# Adafruit_LSM9DS1_Rev_A.net
KiCad netlist of a schematic drawn in EAGLE
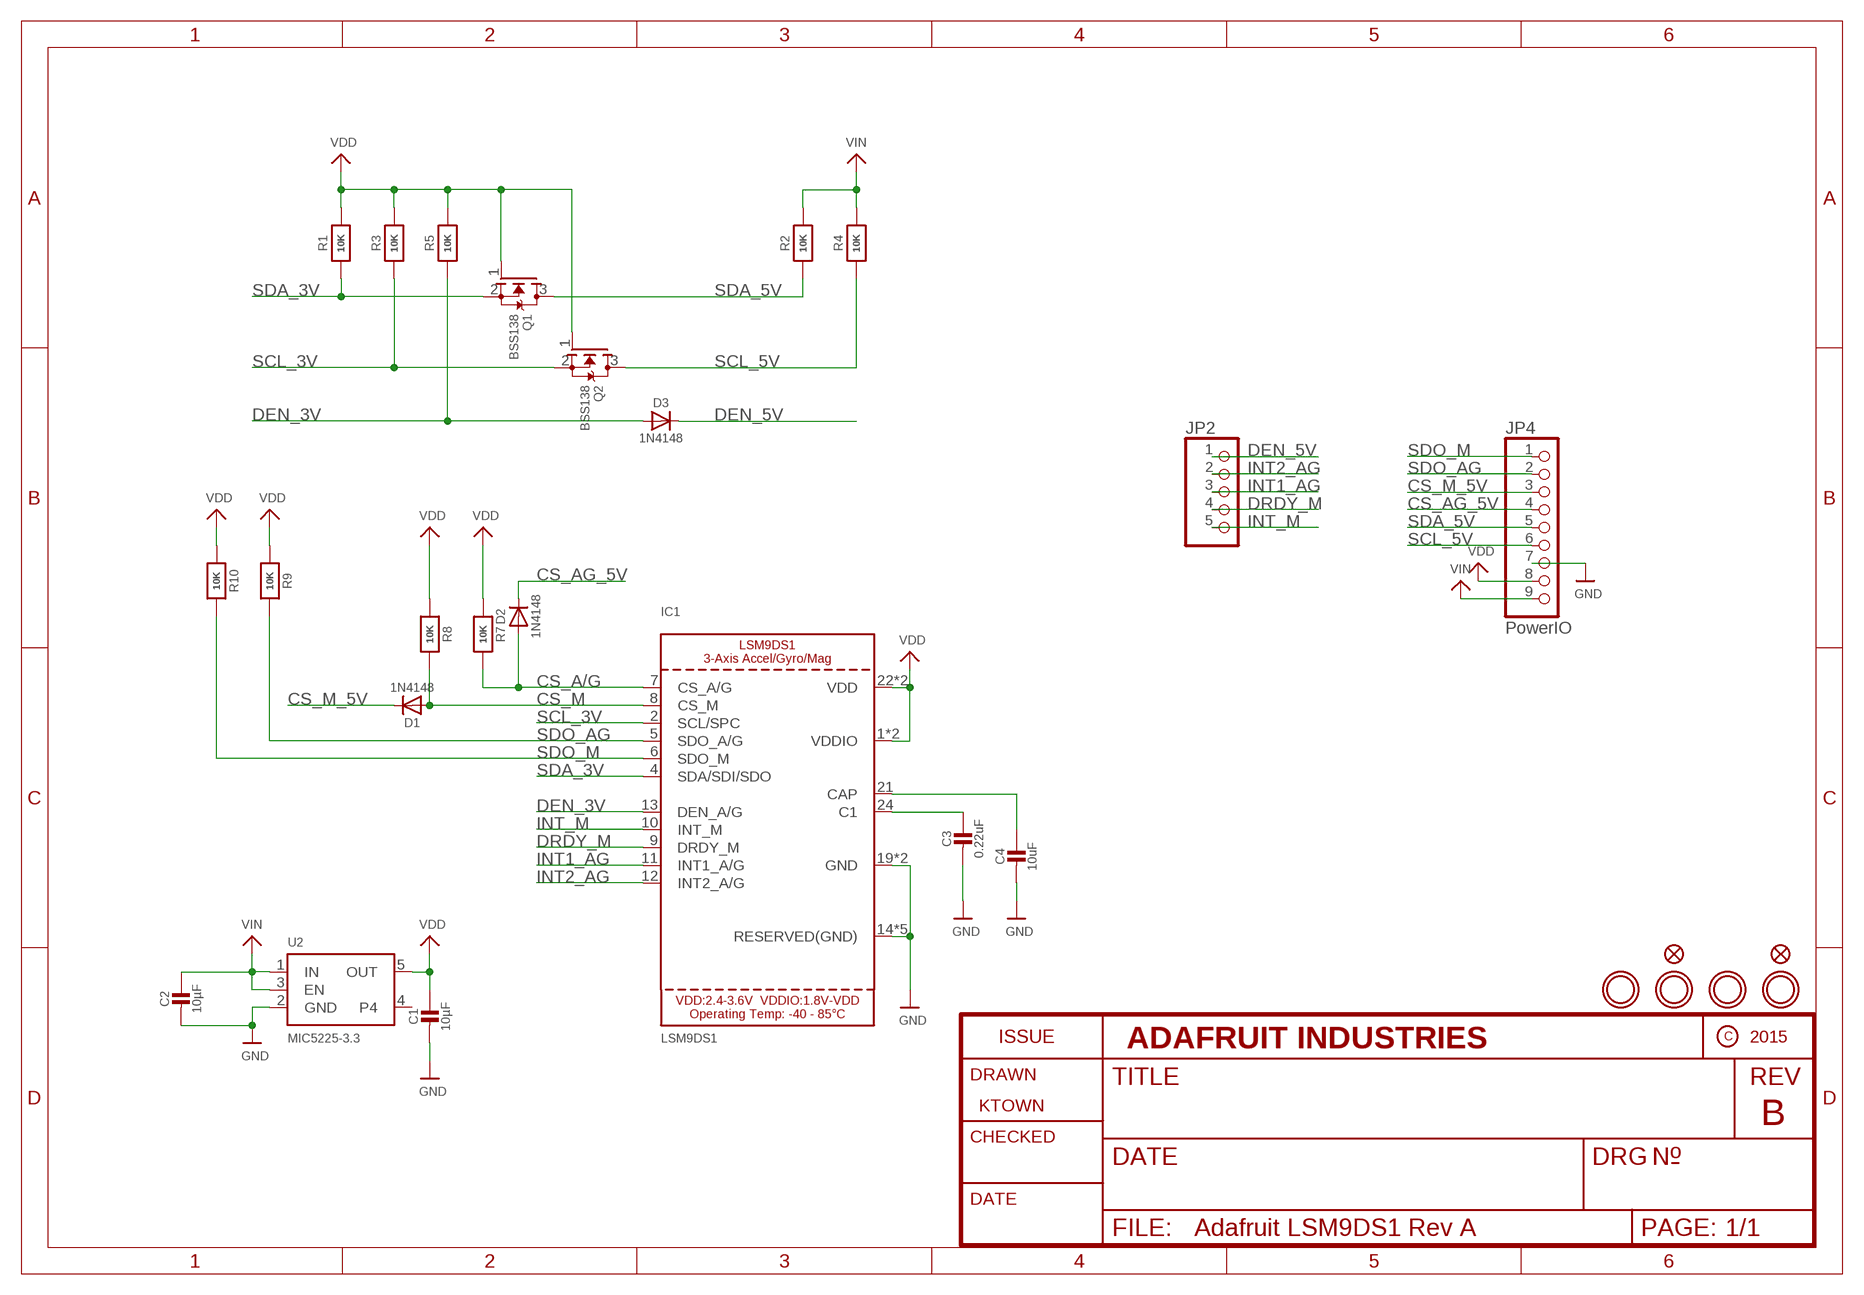
[diagram p0: schematic, sheet 1]

(export (version "E")
  (design (tool "Eeschema 10.0.6"))
  (components
    (comp (ref "C1")
      (value "10µF")
      (footprint "eagle-import:0805-NO")
      (libsource (lib "eagle-import") (part "CAP_CERAMIC0805-NOOUTLINE"))
    )
    (comp (ref "C2")
      (value "10µF")
      (footprint "eagle-import:0805-NO")
      (libsource (lib "eagle-import") (part "CAP_CERAMIC0805-NOOUTLINE"))
    )
    (comp (ref "C3")
      (value "0.22uF")
      (footprint "eagle-import:0805_10MGAP")
      (libsource (lib "eagle-import") (part "CAP_CERAMIC0805_10MGAP"))
    )
    (comp (ref "C4")
      (value "10uF")
      (footprint "eagle-import:0805-NO")
      (libsource (lib "eagle-import") (part "CAP_CERAMIC0805-NOOUTLINE"))
    )
    (comp (ref "D1")
      (value "1N4148")
      (footprint "eagle-import:SOD-323")
      (libsource (lib "eagle-import") (part "DIODESOD-323"))
    )
    (comp (ref "D2")
      (value "1N4148")
      (footprint "eagle-import:SOD-323")
      (libsource (lib "eagle-import") (part "DIODESOD-323"))
    )
    (comp (ref "D3")
      (value "1N4148")
      (footprint "eagle-import:SOD-323")
      (libsource (lib "eagle-import") (part "DIODESOD-323"))
    )
    (comp (ref "FID1")
      (value "FIDUCIAL\"\"")
      (footprint "eagle-import:FIDUCIAL_1MM")
      (libsource (lib "eagle-import") (part "FIDUCIAL{dblquote}{dblquote}"))
    )
    (comp (ref "FID3")
      (value "FIDUCIAL\"\"")
      (footprint "eagle-import:FIDUCIAL_1MM")
      (fields (field (name "BOM") "EXCLUDE"))
      (libsource (lib "eagle-import") (part "FIDUCIAL{dblquote}{dblquote}"))
    )
    (comp (ref "IC1")
      (value "LSM9DS1")
      (footprint "eagle-import:LGA24_3.5X3.1MM")
      (libsource (lib "eagle-import") (part "LSM9DS1"))
    )
    (comp (ref "JP2")
      (value "HEADER-1X570MIL")
      (footprint "eagle-import:1X05_ROUND_70")
      (libsource (lib "eagle-import") (part "HEADER-1X570MIL"))
    )
    (comp (ref "JP4")
      (value "PowerIO")
      (footprint "eagle-import:1X09_ROUND_70")
      (libsource (lib "eagle-import") (part "HEADER-1X970MIL"))
    )
    (comp (ref "Q1")
      (value "BSS138")
      (footprint "eagle-import:SOT23-WIDE")
      (libsource (lib "eagle-import") (part "MOSFET-NWIDE"))
    )
    (comp (ref "Q2")
      (value "BSS138")
      (footprint "eagle-import:SOT23-WIDE")
      (libsource (lib "eagle-import") (part "MOSFET-NWIDE"))
    )
    (comp (ref "R1")
      (value "10K")
      (footprint "eagle-import:0805_10MGAP")
      (libsource (lib "eagle-import") (part "RESISTOR0805_10MGAP"))
    )
    (comp (ref "R2")
      (value "10K")
      (footprint "eagle-import:0805-NO")
      (libsource (lib "eagle-import") (part "RESISTOR0805_NOOUTLINE"))
    )
    (comp (ref "R3")
      (value "10K")
      (footprint "eagle-import:0805-NO")
      (libsource (lib "eagle-import") (part "RESISTOR0805_NOOUTLINE"))
    )
    (comp (ref "R4")
      (value "10K")
      (footprint "eagle-import:0805-NO")
      (libsource (lib "eagle-import") (part "RESISTOR0805_NOOUTLINE"))
    )
    (comp (ref "R5")
      (value "10K")
      (footprint "eagle-import:0805-NO")
      (libsource (lib "eagle-import") (part "RESISTOR0805_NOOUTLINE"))
    )
    (comp (ref "R7")
      (value "10K")
      (footprint "eagle-import:0805-NO")
      (libsource (lib "eagle-import") (part "RESISTOR0805_NOOUTLINE"))
    )
    (comp (ref "R8")
      (value "10K")
      (footprint "eagle-import:0805-NO")
      (libsource (lib "eagle-import") (part "RESISTOR0805_NOOUTLINE"))
    )
    (comp (ref "R9")
      (value "10K")
      (footprint "eagle-import:0805_10MGAP")
      (libsource (lib "eagle-import") (part "RESISTOR0805_10MGAP"))
    )
    (comp (ref "R10")
      (value "10K")
      (footprint "eagle-import:0805-NO")
      (libsource (lib "eagle-import") (part "RESISTOR0805_NOOUTLINE"))
    )
    (comp (ref "U$4")
      (value "MOUNTINGHOLE2.5")
      (footprint "eagle-import:MOUNTINGHOLE_2.5_PLATED")
      (libsource (lib "eagle-import") (part "MOUNTINGHOLE2.5"))
    )
    (comp (ref "U$5")
      (value "MOUNTINGHOLE2.5")
      (footprint "eagle-import:MOUNTINGHOLE_2.5_PLATED")
      (libsource (lib "eagle-import") (part "MOUNTINGHOLE2.5"))
    )
    (comp (ref "U$6")
      (value "MOUNTINGHOLE2.5")
      (footprint "eagle-import:MOUNTINGHOLE_2.5_PLATED")
      (libsource (lib "eagle-import") (part "MOUNTINGHOLE2.5"))
    )
    (comp (ref "U$7")
      (value "MOUNTINGHOLE2.5")
      (footprint "eagle-import:MOUNTINGHOLE_2.5_PLATED")
      (libsource (lib "eagle-import") (part "MOUNTINGHOLE2.5"))
    )
    (comp (ref "U2")
      (value "MIC5225-3.3")
      (footprint "eagle-import:SOT23-5")
      (libsource (lib "eagle-import") (part "VREG_SOT23-5"))
    )
  )
  (nets
    (net (code "1") (name "/CS_AG_5V") (class "Default")
      (node (ref "D2") (pin "C") (pinfunction "C_C") (pintype "passive"))
      (node (ref "JP4") (pin "4") (pinfunction "4_4") (pintype "passive"))
    )
    (net (code "2") (name "/CS_A{slash}G") (class "Default")
      (node (ref "D2") (pin "A") (pinfunction "A_A") (pintype "passive"))
      (node (ref "IC1") (pin "7") (pinfunction "CS_A/G_7") (pintype "bidirectional"))
      (node (ref "R7") (pin "2") (pinfunction "2_2") (pintype "passive"))
    )
    (net (code "3") (name "/CS_M") (class "Default")
      (node (ref "D1") (pin "A") (pinfunction "A_A") (pintype "passive"))
      (node (ref "IC1") (pin "8") (pinfunction "CS_M_8") (pintype "bidirectional"))
      (node (ref "R8") (pin "2") (pinfunction "2_2") (pintype "passive"))
    )
    (net (code "4") (name "/CS_M_5V") (class "Default")
      (node (ref "D1") (pin "C") (pinfunction "C_C") (pintype "passive"))
      (node (ref "JP4") (pin "3") (pinfunction "3_3") (pintype "passive"))
    )
    (net (code "5") (name "/DEN_3V") (class "Default")
      (node (ref "D3") (pin "A") (pinfunction "A_A") (pintype "passive"))
      (node (ref "IC1") (pin "13") (pinfunction "DEN_A/G_13") (pintype "bidirectional"))
      (node (ref "R5") (pin "1") (pinfunction "1_1") (pintype "passive"))
    )
    (net (code "6") (name "/DEN_5V") (class "Default")
      (node (ref "D3") (pin "C") (pinfunction "C_C") (pintype "passive"))
      (node (ref "JP2") (pin "1") (pinfunction "1_1") (pintype "passive"))
    )
    (net (code "7") (name "/DRDY_M") (class "Default")
      (node (ref "IC1") (pin "9") (pinfunction "DRDY_M_9") (pintype "bidirectional"))
      (node (ref "JP2") (pin "4") (pinfunction "4_4") (pintype "passive"))
    )
    (net (code "8") (name "/INT1_AG") (class "Default")
      (node (ref "IC1") (pin "11") (pinfunction "INT1_A/G_11") (pintype "bidirectional"))
      (node (ref "JP2") (pin "3") (pinfunction "3_3") (pintype "passive"))
    )
    (net (code "9") (name "/INT2_AG") (class "Default")
      (node (ref "IC1") (pin "12") (pinfunction "INT2_A/G_12") (pintype "bidirectional"))
      (node (ref "JP2") (pin "2") (pinfunction "2_2") (pintype "passive"))
    )
    (net (code "10") (name "/INT_M") (class "Default")
      (node (ref "IC1") (pin "10") (pinfunction "INT_M_10") (pintype "bidirectional"))
      (node (ref "JP2") (pin "5") (pinfunction "5_5") (pintype "passive"))
    )
    (net (code "11") (name "/SCL_3V") (class "Default")
      (node (ref "IC1") (pin "2") (pinfunction "SCL/SPC_2") (pintype "bidirectional"))
      (node (ref "Q2") (pin "2") (pinfunction "S_2") (pintype "bidirectional"))
      (node (ref "R3") (pin "1") (pinfunction "1_1") (pintype "passive"))
    )
    (net (code "12") (name "/SCL_5V") (class "Default")
      (node (ref "JP4") (pin "6") (pinfunction "6_6") (pintype "passive"))
      (node (ref "Q2") (pin "3") (pinfunction "D_3") (pintype "bidirectional"))
      (node (ref "R4") (pin "1") (pinfunction "1_1") (pintype "passive"))
    )
    (net (code "13") (name "/SDA_3V") (class "Default")
      (node (ref "IC1") (pin "4") (pinfunction "SDA/SDI/SDO_4") (pintype "bidirectional"))
      (node (ref "Q1") (pin "2") (pinfunction "S_2") (pintype "bidirectional"))
      (node (ref "R1") (pin "1") (pinfunction "1_1") (pintype "passive"))
    )
    (net (code "14") (name "/SDA_5V") (class "Default")
      (node (ref "JP4") (pin "5") (pinfunction "5_5") (pintype "passive"))
      (node (ref "Q1") (pin "3") (pinfunction "D_3") (pintype "bidirectional"))
      (node (ref "R2") (pin "1") (pinfunction "1_1") (pintype "passive"))
    )
    (net (code "15") (name "/SDO_AG") (class "Default")
      (node (ref "IC1") (pin "5") (pinfunction "SDO_A/G_5") (pintype "bidirectional"))
      (node (ref "JP4") (pin "2") (pinfunction "2_2") (pintype "passive"))
      (node (ref "R9") (pin "2") (pinfunction "2_2") (pintype "passive"))
    )
    (net (code "16") (name "/SDO_M") (class "Default")
      (node (ref "IC1") (pin "6") (pinfunction "SDO_M_6") (pintype "bidirectional"))
      (node (ref "JP4") (pin "1") (pinfunction "1_1") (pintype "passive"))
      (node (ref "R10") (pin "2") (pinfunction "2_2") (pintype "passive"))
    )
    (net (code "17") (name "GND") (class "Default")
      (node (ref "C1") (pin "2") (pinfunction "2_2") (pintype "passive"))
      (node (ref "C2") (pin "2") (pinfunction "2_2") (pintype "passive"))
      (node (ref "C3") (pin "2") (pinfunction "2_2") (pintype "passive"))
      (node (ref "C4") (pin "2") (pinfunction "2_2") (pintype "passive"))
      (node (ref "IC1") (pin "14") (pinfunction "RESERVED(GND)_14") (pintype "power_in"))
      (node (ref "IC1") (pin "15") (pinfunction "RESERVED(GND)_15") (pintype "power_in"))
      (node (ref "IC1") (pin "16") (pinfunction "RESERVED(GND)_16") (pintype "power_in"))
      (node (ref "IC1") (pin "17") (pinfunction "RESERVED(GND)_17") (pintype "power_in"))
      (node (ref "IC1") (pin "18") (pinfunction "RESERVED(GND)_18") (pintype "power_in"))
      (node (ref "IC1") (pin "19") (pinfunction "GND_19") (pintype "power_in"))
      (node (ref "IC1") (pin "20") (pinfunction "GND_20") (pintype "power_in"))
      (node (ref "JP4") (pin "7") (pinfunction "7_7") (pintype "passive"))
      (node (ref "U2") (pin "2") (pinfunction "GND_2") (pintype "power_in"))
    )
    (net (code "18") (name "Net-(IC1-C1)") (class "Default")
      (node (ref "C3") (pin "1") (pinfunction "1_1") (pintype "passive"))
      (node (ref "IC1") (pin "24") (pinfunction "C1_24") (pintype "bidirectional"))
    )
    (net (code "19") (name "Net-(IC1-CAP)") (class "Default")
      (node (ref "C4") (pin "1") (pinfunction "1_1") (pintype "passive"))
      (node (ref "IC1") (pin "21") (pinfunction "CAP_21") (pintype "bidirectional"))
    )
    (net (code "20") (name "VDD") (class "Default")
      (node (ref "C1") (pin "1") (pinfunction "1_1") (pintype "passive"))
      (node (ref "IC1") (pin "1") (pinfunction "VDDIO_1") (pintype "power_in"))
      (node (ref "IC1") (pin "22") (pinfunction "VDD_22") (pintype "power_in"))
      (node (ref "IC1") (pin "23") (pinfunction "VDD_23") (pintype "power_in"))
      (node (ref "IC1") (pin "3") (pinfunction "VDDIO_3") (pintype "power_in"))
      (node (ref "JP4") (pin "8") (pinfunction "8_8") (pintype "passive"))
      (node (ref "Q1") (pin "1") (pinfunction "G_1") (pintype "bidirectional"))
      (node (ref "Q2") (pin "1") (pinfunction "G_1") (pintype "bidirectional"))
      (node (ref "R1") (pin "2") (pinfunction "2_2") (pintype "passive"))
      (node (ref "R10") (pin "1") (pinfunction "1_1") (pintype "passive"))
      (node (ref "R3") (pin "2") (pinfunction "2_2") (pintype "passive"))
      (node (ref "R5") (pin "2") (pinfunction "2_2") (pintype "passive"))
      (node (ref "R7") (pin "1") (pinfunction "1_1") (pintype "passive"))
      (node (ref "R8") (pin "1") (pinfunction "1_1") (pintype "passive"))
      (node (ref "R9") (pin "1") (pinfunction "1_1") (pintype "passive"))
      (node (ref "U2") (pin "5") (pinfunction "OUT_5") (pintype "power_in"))
    )
    (net (code "21") (name "VIN") (class "Default")
      (node (ref "C2") (pin "1") (pinfunction "1_1") (pintype "passive"))
      (node (ref "JP4") (pin "9") (pinfunction "9_9") (pintype "passive"))
      (node (ref "R2") (pin "2") (pinfunction "2_2") (pintype "passive"))
      (node (ref "R4") (pin "2") (pinfunction "2_2") (pintype "passive"))
      (node (ref "U2") (pin "1") (pinfunction "IN_1") (pintype "power_in"))
      (node (ref "U2") (pin "3") (pinfunction "EN_3") (pintype "input"))
    )
    (net (code "22") (name "unconnected-(U2-P4-Pad4)") (class "Default")
      (node (ref "U2") (pin "4") (pinfunction "P4_4") (pintype "bidirectional"))
    )
  )
)
